# BHOnOfreBoard_Rev2_Charly.net
KiCad netlist of a schematic drawn in EAGLE
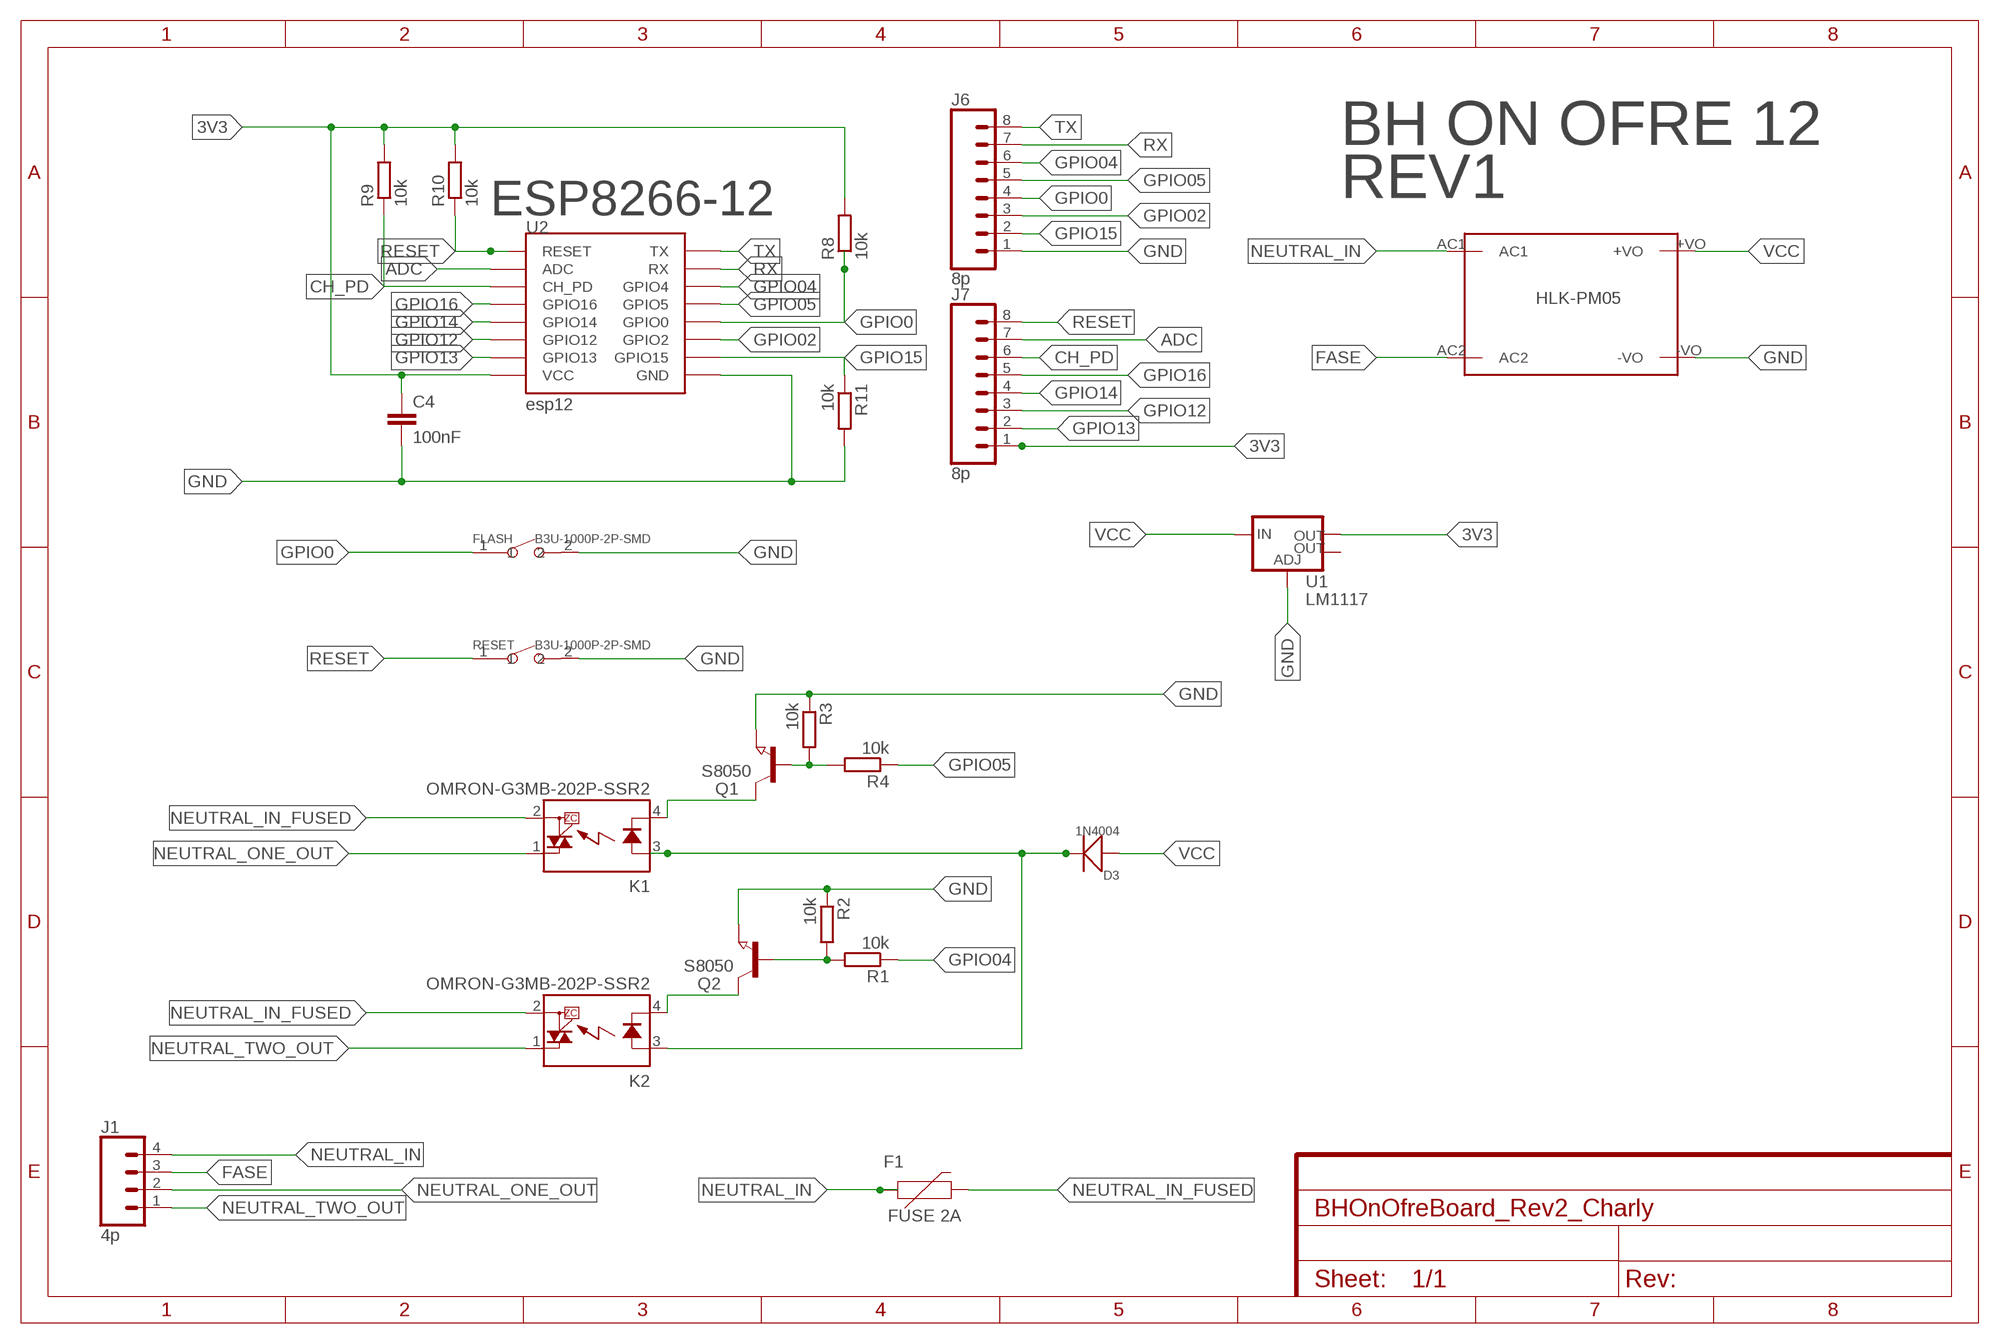
[diagram p0: schematic, sheet 1]

(export (version "E")
  (design (tool "Eeschema 10.0.6"))
  (components
    (comp (ref "C4")
      (value "100nF")
      (footprint "eagle-import:0603")
      (libsource (lib "eagle-import") (part "10NF-0603-50V-10%"))
    )
    (comp (ref "D3")
      (value "1N4004")
      (footprint "eagle-import:DO-214AC")
      (fields (field (name "MPN") "1N4007"))
      (libsource (lib "eagle-import") (part "DIODE-GEN-PURPOSE-1KV-1A(DO-214AC)"))
    )
    (comp (ref "F1")
      (value "FUSE 2A")
      (footprint "eagle-import:PTH")
      (libsource (lib "eagle-import") (part "PPTC_PTH"))
    )
    (comp (ref "FLASH")
      (value "B3U-1000P-2P-SMD")
      (footprint "eagle-import:SW2-2.6-3.0X2.5X1.2+0.4MM")
      (libsource (lib "eagle-import") (part "SMD-BUTTON(2P-3.0X2.5X1.2+0.4MM)-B3U-1000P-2P-SMD"))
    )
    (comp (ref "J1")
      (value "4p")
      (footprint "eagle-import:SCREWTERMINAL-3.5MM-4")
      (libsource (lib "eagle-import") (part "CONN_04SCREW"))
    )
    (comp (ref "J6")
      (value "8p")
      (footprint "eagle-import:1X08")
      (libsource (lib "eagle-import") (part "CONN_08{dblquote}"))
    )
    (comp (ref "J7")
      (value "8p")
      (footprint "eagle-import:1X08")
      (libsource (lib "eagle-import") (part "CONN_08{dblquote}"))
    )
    (comp (ref "K1")
      (value "OMRON-G3MB-202P-SSR2")
      (footprint "eagle-import:OMRON-G3MB-202P-SSR")
      (fields (field (name "MPN") "S202S02F"))
      (libsource (lib "eagle-import") (part "OMRON-G3MB-202P-SSR2"))
    )
    (comp (ref "K2")
      (value "OMRON-G3MB-202P-SSR2")
      (footprint "eagle-import:OMRON-G3MB-202P-SSR")
      (fields (field (name "MPN") "S202S02F"))
      (libsource (lib "eagle-import") (part "OMRON-G3MB-202P-SSR2"))
    )
    (comp (ref "Q1")
      (value "S8050")
      (footprint "eagle-import:SOT23")
      (libsource (lib "eagle-import") (part "NPN-TRANSISTOR_SOT23"))
    )
    (comp (ref "Q2")
      (value "S8050")
      (footprint "eagle-import:SOT23")
      (libsource (lib "eagle-import") (part "NPN-TRANSISTOR_SOT23"))
    )
    (comp (ref "R1")
      (value "10k")
      (footprint "eagle-import:R0603")
      (libsource (lib "eagle-import") (part "R-EU_R0603"))
    )
    (comp (ref "R2")
      (value "10k")
      (footprint "eagle-import:R0603")
      (libsource (lib "eagle-import") (part "R-EU_R0603"))
    )
    (comp (ref "R3")
      (value "10k")
      (footprint "eagle-import:R0603")
      (libsource (lib "eagle-import") (part "R-EU_R0603"))
    )
    (comp (ref "R4")
      (value "10k")
      (footprint "eagle-import:R0603")
      (libsource (lib "eagle-import") (part "R-EU_R0603"))
    )
    (comp (ref "R8")
      (value "10k")
      (footprint "eagle-import:R0603")
      (libsource (lib "eagle-import") (part "R-EU_R0603"))
    )
    (comp (ref "R9")
      (value "10k")
      (footprint "eagle-import:R0603")
      (libsource (lib "eagle-import") (part "R-EU_R0603"))
    )
    (comp (ref "R10")
      (value "10k")
      (footprint "eagle-import:R0603")
      (libsource (lib "eagle-import") (part "R-EU_R0603"))
    )
    (comp (ref "R11")
      (value "10k")
      (footprint "eagle-import:R0603")
      (libsource (lib "eagle-import") (part "R-EU_R0603"))
    )
    (comp (ref "RESET")
      (value "B3U-1000P-2P-SMD")
      (footprint "eagle-import:SW2-2.6-3.0X2.5X1.2+0.4MM")
      (libsource (lib "eagle-import") (part "SMD-BUTTON(2P-3.0X2.5X1.2+0.4MM)-B3U-1000P-2P-SMD"))
    )
    (comp (ref "U$2")
      (value "HLK-PM03")
      (footprint "eagle-import:HLK-PM03")
      (libsource (lib "eagle-import") (part "HLK-PM03"))
    )
    (comp (ref "U1")
      (value "LM1117")
      (footprint "eagle-import:SOT223")
      (libsource (lib "eagle-import") (part "V_REG_LM1117SOT223"))
    )
    (comp (ref "U2")
      (value "esp12")
      (footprint "eagle-import:ESP12-SMD")
      (libsource (lib "eagle-import") (part "ESP12SMD"))
    )
  )
  (nets
    (net (code "1") (name "3V3") (class "Default")
      (node (ref "C4") (pin "1") (pinfunction "1_1") (pintype "passive"))
      (node (ref "J7") (pin "1") (pinfunction "1_1") (pintype "passive"))
      (node (ref "R10") (pin "2") (pinfunction "2_2") (pintype "passive"))
      (node (ref "R8") (pin "2") (pinfunction "2_2") (pintype "passive"))
      (node (ref "R9") (pin "2") (pinfunction "2_2") (pintype "passive"))
      (node (ref "U1") (pin "2") (pinfunction "OUT_2") (pintype "output"))
      (node (ref "U2") (pin "VCC") (pinfunction "VCC_VCC") (pintype "bidirectional"))
    )
    (net (code "2") (name "ADC") (class "Default")
      (node (ref "J7") (pin "7") (pinfunction "7_7") (pintype "passive"))
      (node (ref "U2") (pin "ADC") (pinfunction "ADC_ADC") (pintype "bidirectional"))
    )
    (net (code "3") (name "CH_PD") (class "Default")
      (node (ref "J7") (pin "6") (pinfunction "6_6") (pintype "passive"))
      (node (ref "R9") (pin "1") (pinfunction "1_1") (pintype "passive"))
      (node (ref "U2") (pin "CH_PD") (pinfunction "CH_PD_CH_PD") (pintype "bidirectional"))
    )
    (net (code "4") (name "FASE") (class "Default")
      (node (ref "J1") (pin "3") (pinfunction "3_3") (pintype "passive"))
      (node (ref "U$2") (pin "AC2") (pinfunction "AC2_AC2") (pintype "bidirectional"))
    )
    (net (code "5") (name "GND") (class "Default")
      (node (ref "C4") (pin "2") (pinfunction "2_2") (pintype "passive"))
      (node (ref "FLASH") (pin "2") (pinfunction "2_2") (pintype "bidirectional"))
      (node (ref "J6") (pin "1") (pinfunction "1_1") (pintype "passive"))
      (node (ref "Q1") (pin "2") (pinfunction "E_2") (pintype "passive"))
      (node (ref "Q2") (pin "2") (pinfunction "E_2") (pintype "passive"))
      (node (ref "R11") (pin "2") (pinfunction "2_2") (pintype "passive"))
      (node (ref "R2") (pin "1") (pinfunction "1_1") (pintype "passive"))
      (node (ref "R3") (pin "1") (pinfunction "1_1") (pintype "passive"))
      (node (ref "RESET") (pin "2") (pinfunction "2_2") (pintype "bidirectional"))
      (node (ref "U$2") (pin "-VO") (pinfunction "-VO_-VO") (pintype "bidirectional"))
      (node (ref "U1") (pin "1") (pinfunction "ADJ_1") (pintype "input"))
      (node (ref "U2") (pin "GND") (pinfunction "GND_GND") (pintype "bidirectional"))
    )
    (net (code "6") (name "GPIO0") (class "Default")
      (node (ref "FLASH") (pin "1") (pinfunction "1_1") (pintype "bidirectional"))
      (node (ref "J6") (pin "4") (pinfunction "4_4") (pintype "passive"))
      (node (ref "R8") (pin "1") (pinfunction "1_1") (pintype "passive"))
      (node (ref "U2") (pin "GPIO0") (pinfunction "GPIO0_GPIO0") (pintype "bidirectional"))
    )
    (net (code "7") (name "GPIO02") (class "Default")
      (node (ref "J6") (pin "3") (pinfunction "3_3") (pintype "passive"))
      (node (ref "U2") (pin "GPIO2") (pinfunction "GPIO2_GPIO2") (pintype "bidirectional"))
    )
    (net (code "8") (name "GPIO04") (class "Default")
      (node (ref "J6") (pin "6") (pinfunction "6_6") (pintype "passive"))
      (node (ref "R1") (pin "1") (pinfunction "1_1") (pintype "passive"))
      (node (ref "U2") (pin "GPIO4") (pinfunction "GPIO4_GPIO4") (pintype "bidirectional"))
    )
    (net (code "9") (name "GPIO05") (class "Default")
      (node (ref "J6") (pin "5") (pinfunction "5_5") (pintype "passive"))
      (node (ref "R4") (pin "1") (pinfunction "1_1") (pintype "passive"))
      (node (ref "U2") (pin "GPIO5") (pinfunction "GPIO5_GPIO5") (pintype "bidirectional"))
    )
    (net (code "10") (name "GPIO12") (class "Default")
      (node (ref "J7") (pin "3") (pinfunction "3_3") (pintype "passive"))
      (node (ref "U2") (pin "GPIO12") (pinfunction "GPIO12_GPIO12") (pintype "bidirectional"))
    )
    (net (code "11") (name "GPIO13") (class "Default")
      (node (ref "J7") (pin "2") (pinfunction "2_2") (pintype "passive"))
      (node (ref "U2") (pin "GPIO13") (pinfunction "GPIO13_GPIO13") (pintype "bidirectional"))
    )
    (net (code "12") (name "GPIO14") (class "Default")
      (node (ref "J7") (pin "4") (pinfunction "4_4") (pintype "passive"))
      (node (ref "U2") (pin "GPIO14") (pinfunction "GPIO14_GPIO14") (pintype "bidirectional"))
    )
    (net (code "13") (name "GPIO15") (class "Default")
      (node (ref "J6") (pin "2") (pinfunction "2_2") (pintype "passive"))
      (node (ref "R11") (pin "1") (pinfunction "1_1") (pintype "passive"))
      (node (ref "U2") (pin "GPIO15") (pinfunction "GPIO15_GPIO15") (pintype "bidirectional"))
    )
    (net (code "14") (name "GPIO16") (class "Default")
      (node (ref "J7") (pin "5") (pinfunction "5_5") (pintype "passive"))
      (node (ref "U2") (pin "GPIO16") (pinfunction "GPIO16_GPIO16") (pintype "bidirectional"))
    )
    (net (code "15") (name "NEUTRAL_IN") (class "Default")
      (node (ref "F1") (pin "P$1") (pinfunction "1_P$1") (pintype "bidirectional"))
      (node (ref "J1") (pin "4") (pinfunction "4_4") (pintype "passive"))
      (node (ref "U$2") (pin "AC1") (pinfunction "AC1_AC1") (pintype "bidirectional"))
    )
    (net (code "16") (name "NEUTRAL_IN_FUSED") (class "Default")
      (node (ref "F1") (pin "P$2") (pinfunction "2_P$2") (pintype "bidirectional"))
      (node (ref "K1") (pin "2") (pinfunction "DS2_2") (pintype "passive"))
      (node (ref "K2") (pin "2") (pinfunction "DS2_2") (pintype "passive"))
    )
    (net (code "17") (name "NEUTRAL_ONE_OUT") (class "Default")
      (node (ref "J1") (pin "2") (pinfunction "2_2") (pintype "passive"))
      (node (ref "K1") (pin "1") (pinfunction "DS1_1") (pintype "passive"))
    )
    (net (code "18") (name "NEUTRAL_TWO_OUT") (class "Default")
      (node (ref "J1") (pin "1") (pinfunction "1_1") (pintype "passive"))
      (node (ref "K2") (pin "1") (pinfunction "DS1_1") (pintype "passive"))
    )
    (net (code "19") (name "Net-(D3--)") (class "Default")
      (node (ref "D3") (pin "2") (pinfunction "-_2") (pintype "passive"))
      (node (ref "K1") (pin "3") (pinfunction "A_3") (pintype "passive"))
      (node (ref "K2") (pin "3") (pinfunction "A_3") (pintype "passive"))
    )
    (net (code "20") (name "Net-(K1-K)") (class "Default")
      (node (ref "K1") (pin "4") (pinfunction "K_4") (pintype "passive"))
      (node (ref "Q1") (pin "3") (pinfunction "C_3") (pintype "passive"))
    )
    (net (code "21") (name "Net-(K2-K)") (class "Default")
      (node (ref "K2") (pin "4") (pinfunction "K_4") (pintype "passive"))
      (node (ref "Q2") (pin "3") (pinfunction "C_3") (pintype "passive"))
    )
    (net (code "22") (name "Net-(Q1-B)") (class "Default")
      (node (ref "Q1") (pin "1") (pinfunction "B_1") (pintype "passive"))
      (node (ref "R3") (pin "2") (pinfunction "2_2") (pintype "passive"))
      (node (ref "R4") (pin "2") (pinfunction "2_2") (pintype "passive"))
    )
    (net (code "23") (name "Net-(Q2-B)") (class "Default")
      (node (ref "Q2") (pin "1") (pinfunction "B_1") (pintype "passive"))
      (node (ref "R1") (pin "2") (pinfunction "2_2") (pintype "passive"))
      (node (ref "R2") (pin "2") (pinfunction "2_2") (pintype "passive"))
    )
    (net (code "24") (name "RESET") (class "Default")
      (node (ref "J7") (pin "8") (pinfunction "8_8") (pintype "passive"))
      (node (ref "R10") (pin "1") (pinfunction "1_1") (pintype "passive"))
      (node (ref "RESET") (pin "1") (pinfunction "1_1") (pintype "bidirectional"))
      (node (ref "U2") (pin "RESET") (pinfunction "RESET_RESET") (pintype "bidirectional"))
    )
    (net (code "25") (name "RX") (class "Default")
      (node (ref "J6") (pin "7") (pinfunction "7_7") (pintype "passive"))
      (node (ref "U2") (pin "RXD0") (pinfunction "RX_RXD0") (pintype "bidirectional"))
    )
    (net (code "26") (name "TX") (class "Default")
      (node (ref "J6") (pin "8") (pinfunction "8_8") (pintype "passive"))
      (node (ref "U2") (pin "TXD0") (pinfunction "TX_TXD0") (pintype "bidirectional"))
    )
    (net (code "27") (name "VCC") (class "Default")
      (node (ref "D3") (pin "1") (pinfunction "+_1") (pintype "passive"))
      (node (ref "U$2") (pin "+VO") (pinfunction "+VO_+VO") (pintype "bidirectional"))
      (node (ref "U1") (pin "3") (pinfunction "IN_3") (pintype "input"))
    )
    (net (code "28") (name "unconnected-(U1-OUT-Pad4)") (class "Default")
      (node (ref "U1") (pin "4") (pinfunction "OUT_4") (pintype "output"))
    )
  )
)
